# Lamp2.net
KiCad netlist of a schematic drawn in EAGLE
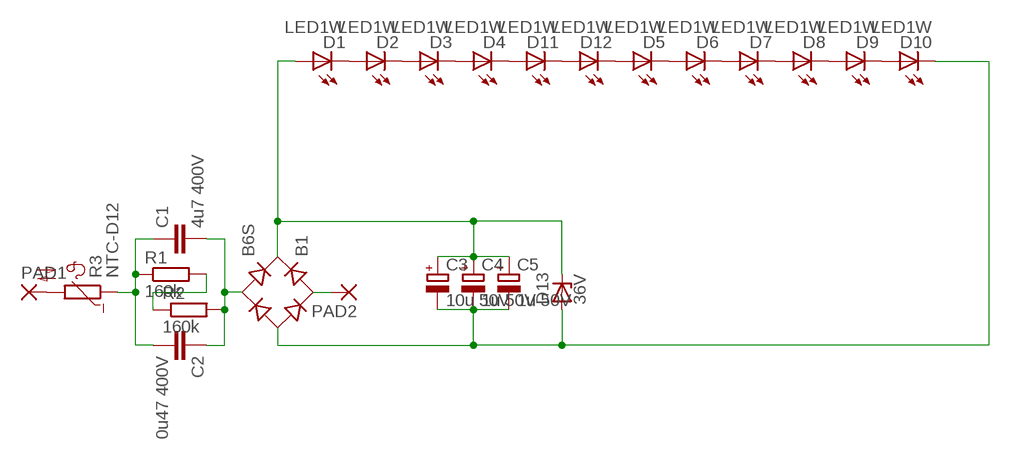
[diagram p0: schematic, sheet 1]

(export (version "E")
  (design (tool "Eeschema 10.0.6"))
  (components
    (comp (ref "B1")
      (value "B6S")
      (footprint "eagle-import:MBS")
      (libsource (lib "eagle-import") (part "BS6"))
    )
    (comp (ref "C1")
      (value "4u7 400V")
      (footprint "eagle-import:C275-134X316")
      (libsource (lib "eagle-import") (part "C-EU275-134X316"))
    )
    (comp (ref "C2")
      (value "0u47 400V")
      (footprint "eagle-import:C150-054X183")
      (libsource (lib "eagle-import") (part "C-EU150-054X183"))
    )
    (comp (ref "C3")
      (value "10u 50V")
      (footprint "eagle-import:E2,5-5")
      (libsource (lib "eagle-import") (part "CPOL-EUE2.5-5"))
    )
    (comp (ref "C4")
      (value "1u 50V")
      (footprint "eagle-import:E2,5-5")
      (libsource (lib "eagle-import") (part "CPOL-EUE2.5-5"))
    )
    (comp (ref "C5")
      (value "1u 50V")
      (footprint "eagle-import:E2,5-5")
      (libsource (lib "eagle-import") (part "CPOL-EUE2.5-5"))
    )
    (comp (ref "D1")
      (value "LED1W")
      (footprint "eagle-import:LED-1W")
      (libsource (lib "eagle-import") (part "LED1W"))
    )
    (comp (ref "D2")
      (value "LED1W")
      (footprint "eagle-import:LED-1W")
      (libsource (lib "eagle-import") (part "LED1W"))
    )
    (comp (ref "D3")
      (value "LED1W")
      (footprint "eagle-import:LED-1W")
      (libsource (lib "eagle-import") (part "LED1W"))
    )
    (comp (ref "D4")
      (value "LED1W")
      (footprint "eagle-import:LED-1W")
      (libsource (lib "eagle-import") (part "LED1W"))
    )
    (comp (ref "D5")
      (value "LED1W")
      (footprint "eagle-import:LED-1W")
      (libsource (lib "eagle-import") (part "LED1W"))
    )
    (comp (ref "D6")
      (value "LED1W")
      (footprint "eagle-import:LED-1W")
      (libsource (lib "eagle-import") (part "LED1W"))
    )
    (comp (ref "D7")
      (value "LED1W")
      (footprint "eagle-import:LED-1W")
      (libsource (lib "eagle-import") (part "LED1W"))
    )
    (comp (ref "D8")
      (value "LED1W")
      (footprint "eagle-import:LED-1W")
      (libsource (lib "eagle-import") (part "LED1W"))
    )
    (comp (ref "D9")
      (value "LED1W")
      (footprint "eagle-import:LED-1W")
      (libsource (lib "eagle-import") (part "LED1W"))
    )
    (comp (ref "D10")
      (value "LED1W")
      (footprint "eagle-import:LED-1W")
      (libsource (lib "eagle-import") (part "LED1W"))
    )
    (comp (ref "D11")
      (value "LED1W")
      (footprint "eagle-import:LED-1W")
      (libsource (lib "eagle-import") (part "LED1W"))
    )
    (comp (ref "D12")
      (value "LED1W")
      (footprint "eagle-import:LED-1W")
      (libsource (lib "eagle-import") (part "LED1W"))
    )
    (comp (ref "D13")
      (value "36V")
      (footprint "eagle-import:ZDIO-5")
      (libsource (lib "eagle-import") (part "ZENER-DIODEZD-5"))
    )
    (comp (ref "PAD1")
      (value "3,81/1,4")
      (footprint "eagle-import:3,81_1,4")
      (libsource (lib "eagle-import") (part "3,81/1,4"))
    )
    (comp (ref "PAD2")
      (value "3,81/1,4")
      (footprint "eagle-import:3,81_1,4")
      (libsource (lib "eagle-import") (part "3,81/1,4"))
    )
    (comp (ref "R1")
      (value "160k")
      (footprint "eagle-import:0204_5")
      (libsource (lib "eagle-import") (part "R-EU_0204/5"))
    )
    (comp (ref "R2")
      (value "160k")
      (footprint "eagle-import:0204_5")
      (libsource (lib "eagle-import") (part "R-EU_0204/5"))
    )
    (comp (ref "R3")
      (value "NTC-D12")
      (footprint "eagle-import:NTC-D12")
      (libsource (lib "eagle-import") (part "NTC-D12"))
    )
  )
  (nets
    (net (code "1") (name "Net-(B1-Pad+)") (class "Default")
      (node (ref "B1") (pin "+") (pinfunction "+_+") (pintype "passive"))
      (node (ref "C3") (pin "+") (pinfunction "+_+") (pintype "passive"))
      (node (ref "C4") (pin "+") (pinfunction "+_+") (pintype "passive"))
      (node (ref "C5") (pin "+") (pinfunction "+_+") (pintype "passive"))
      (node (ref "D1") (pin "A") (pinfunction "A_A") (pintype "passive"))
      (node (ref "D13") (pin "C") (pinfunction "C_C") (pintype "passive"))
    )
    (net (code "2") (name "Net-(B1-PadAC2)") (class "Default")
      (node (ref "B1") (pin "AC2") (pinfunction "AC2_AC2") (pintype "passive"))
      (node (ref "C1") (pin "2") (pinfunction "2_2") (pintype "passive"))
      (node (ref "C2") (pin "1") (pinfunction "1_1") (pintype "passive"))
      (node (ref "R2") (pin "2") (pinfunction "2_2") (pintype "passive"))
    )
    (net (code "3") (name "Net-(C1-Pad1)") (class "Default")
      (node (ref "C1") (pin "1") (pinfunction "1_1") (pintype "passive"))
      (node (ref "C2") (pin "2") (pinfunction "2_2") (pintype "passive"))
      (node (ref "R1") (pin "1") (pinfunction "1_1") (pintype "passive"))
      (node (ref "R3") (pin "1") (pinfunction "1_1") (pintype "passive"))
    )
    (net (code "4") (name "Net-(D1-C)") (class "Default")
      (node (ref "D1") (pin "K") (pinfunction "C_K") (pintype "passive"))
      (node (ref "D2") (pin "A") (pinfunction "A_A") (pintype "passive"))
    )
    (net (code "5") (name "Net-(D2-C)") (class "Default")
      (node (ref "D2") (pin "K") (pinfunction "C_K") (pintype "passive"))
      (node (ref "D3") (pin "A") (pinfunction "A_A") (pintype "passive"))
    )
    (net (code "6") (name "Net-(D3-C)") (class "Default")
      (node (ref "D3") (pin "K") (pinfunction "C_K") (pintype "passive"))
      (node (ref "D4") (pin "A") (pinfunction "A_A") (pintype "passive"))
    )
    (net (code "7") (name "Net-(D4-C)") (class "Default")
      (node (ref "D11") (pin "A") (pinfunction "A_A") (pintype "passive"))
      (node (ref "D4") (pin "K") (pinfunction "C_K") (pintype "passive"))
    )
    (net (code "8") (name "Net-(D5-C)") (class "Default")
      (node (ref "D5") (pin "K") (pinfunction "C_K") (pintype "passive"))
      (node (ref "D6") (pin "A") (pinfunction "A_A") (pintype "passive"))
    )
    (net (code "9") (name "Net-(D6-C)") (class "Default")
      (node (ref "D6") (pin "K") (pinfunction "C_K") (pintype "passive"))
      (node (ref "D7") (pin "A") (pinfunction "A_A") (pintype "passive"))
    )
    (net (code "10") (name "Net-(D7-C)") (class "Default")
      (node (ref "D7") (pin "K") (pinfunction "C_K") (pintype "passive"))
      (node (ref "D8") (pin "A") (pinfunction "A_A") (pintype "passive"))
    )
    (net (code "11") (name "Net-(D8-C)") (class "Default")
      (node (ref "D8") (pin "K") (pinfunction "C_K") (pintype "passive"))
      (node (ref "D9") (pin "A") (pinfunction "A_A") (pintype "passive"))
    )
    (net (code "12") (name "Net-(D9-C)") (class "Default")
      (node (ref "D10") (pin "A") (pinfunction "A_A") (pintype "passive"))
      (node (ref "D9") (pin "K") (pinfunction "C_K") (pintype "passive"))
    )
    (net (code "13") (name "Net-(D10-C)") (class "Default")
      (node (ref "B1") (pin "-") (pinfunction "-_-") (pintype "passive"))
      (node (ref "C3") (pin "-") (pinfunction "-_-") (pintype "passive"))
      (node (ref "C4") (pin "-") (pinfunction "-_-") (pintype "passive"))
      (node (ref "C5") (pin "-") (pinfunction "-_-") (pintype "passive"))
      (node (ref "D10") (pin "K") (pinfunction "C_K") (pintype "passive"))
      (node (ref "D13") (pin "A") (pinfunction "A_A") (pintype "passive"))
    )
    (net (code "14") (name "Net-(D11-C)") (class "Default")
      (node (ref "D11") (pin "K") (pinfunction "C_K") (pintype "passive"))
      (node (ref "D12") (pin "A") (pinfunction "A_A") (pintype "passive"))
    )
    (net (code "15") (name "Net-(D12-C)") (class "Default")
      (node (ref "D12") (pin "K") (pinfunction "C_K") (pintype "passive"))
      (node (ref "D5") (pin "A") (pinfunction "A_A") (pintype "passive"))
    )
    (net (code "16") (name "Net-(PAD1-P)") (class "Default")
      (node (ref "PAD1") (pin "1") (pinfunction "P_1") (pintype "passive"))
      (node (ref "R3") (pin "2") (pinfunction "2_2") (pintype "passive"))
    )
    (net (code "17") (name "Net-(PAD2-P)") (class "Default")
      (node (ref "B1") (pin "AC1") (pinfunction "AC1_AC1") (pintype "passive"))
      (node (ref "PAD2") (pin "1") (pinfunction "P_1") (pintype "passive"))
    )
    (net (code "18") (name "Net-(R1-Pad2)") (class "Default")
      (node (ref "R1") (pin "2") (pinfunction "2_2") (pintype "passive"))
      (node (ref "R2") (pin "1") (pinfunction "1_1") (pintype "passive"))
    )
  )
)
